# RELAY4.net
KiCad netlist of a schematic drawn in Altium Designer
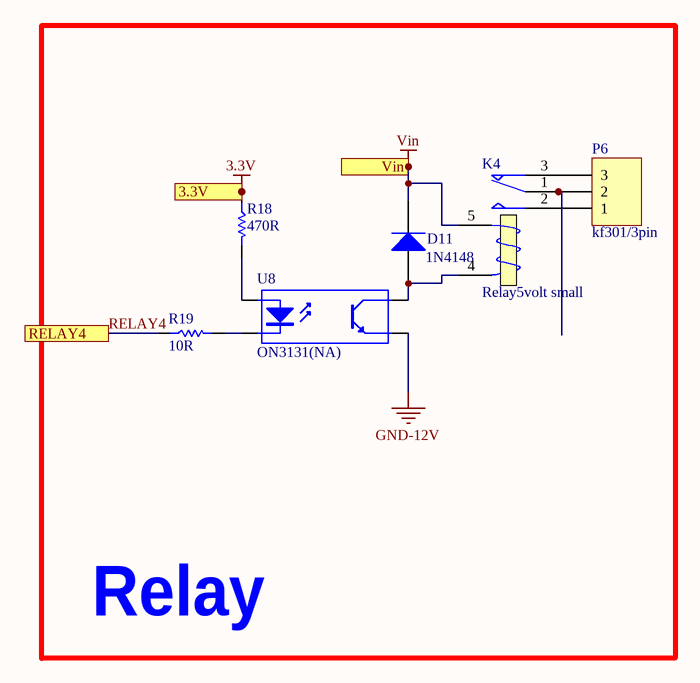
[diagram p0: RELAY4.SchDoc]

(export (version "E")
  (design (tool "Eeschema 10.0.6"))
  (components
    (comp (ref "D11")
      (value "1N4148")
      (footprint "sod123")
      (description "1 Amp General Purpose Rectifier")
      (fields (field (name "PUBLISHER") "Altium Limited"))
      (libsource (lib "Miscellaneous Devices") (part "Diode 1N4007"))
    )
    (comp (ref "K4")
      (value "Relay5volt small")
      (footprint "relay5_childern")
      (description "SPDT Relay")
      (fields (field (name "PUBLISHER") "Altium Limited"))
      (libsource (lib "FLIB") (part "Relay"))
    )
    (comp (ref "P6")
      (value "kf301/3pin")
      (footprint "Blue Connector 1*3 -kf301")
      (fields (field (name "PUBLISHER") "Altium Limited"))
      (libsource (lib "Miscellaneous Connectors") (part "Header 3"))
    )
    (comp (ref "R18")
      (value "470R")
      (footprint "0805/resistor")
      (description "Resistor")
      (fields (field (name "TOLERANCE") "5%") (field (name "POWER") "1/8 W"))
      (libsource (lib "skille") (part "Resistor"))
    )
    (comp (ref "R19")
      (value "10R")
      (footprint "0805/resistor")
      (description "Resistor")
      (fields (field (name "TOLERANCE") "5%") (field (name "POWER") "1/8 W"))
      (libsource (lib "skille") (part "Resistor"))
    )
    (comp (ref "U8")
      (value "ON3131(NA)")
      (footprint "OPTO_COUPLER")
      (description "4-Pin Phototransistor Optocoupler")
      (fields (field (name "PUBLISHER") "Altium Limited"))
      (libsource (lib "skille") (part "Optoisolator1"))
    )
  )
  (nets
    (net (code "1") (name "/RELAY4") (class "Default")
      (node (ref "R19") (pin "1") (pinfunction "1_1") (pintype "passive"))
    )
    (net (code "2") (name "3.3V") (class "Default")
      (node (ref "R18") (pin "1") (pinfunction "1_1") (pintype "passive"))
    )
    (net (code "3") (name "GND-12V") (class "Default")
      (node (ref "U8") (pin "3") (pinfunction "E_3") (pintype "passive"))
    )
    (net (code "4") (name "Net-(K4-COM)") (class "Default")
      (node (ref "K4") (pin "1") (pinfunction "COM_1") (pintype "passive"))
      (node (ref "P6") (pin "2") (pinfunction "2_2") (pintype "passive"))
    )
    (net (code "5") (name "Net-(K4-NO)") (class "Default")
      (node (ref "K4") (pin "2") (pinfunction "NO_2") (pintype "passive"))
      (node (ref "P6") (pin "1") (pinfunction "1_1") (pintype "passive"))
    )
    (net (code "6") (name "Net-(K4-T1)") (class "Default")
      (node (ref "K4") (pin "3") (pinfunction "T1_3") (pintype "passive"))
      (node (ref "P6") (pin "3") (pinfunction "3_3") (pintype "passive"))
    )
    (net (code "7") (name "Net-(K4-T2)") (class "Default")
      (node (ref "D11") (pin "A") (pinfunction "A_A") (pintype "passive"))
      (node (ref "K4") (pin "4") (pinfunction "T2_4") (pintype "passive"))
      (node (ref "U8") (pin "4") (pinfunction "C_4") (pintype "passive"))
    )
    (net (code "8") (name "Net-(U8-A)") (class "Default")
      (node (ref "R18") (pin "2") (pinfunction "2_2") (pintype "passive"))
      (node (ref "U8") (pin "1") (pinfunction "A_1") (pintype "passive"))
    )
    (net (code "9") (name "Net-(U8-K)") (class "Default")
      (node (ref "R19") (pin "2") (pinfunction "2_2") (pintype "passive"))
      (node (ref "U8") (pin "2") (pinfunction "K_2") (pintype "passive"))
    )
    (net (code "10") (name "Vin") (class "Default")
      (node (ref "D11") (pin "K") (pinfunction "K_K") (pintype "passive"))
      (node (ref "K4") (pin "5") (pinfunction "5_5") (pintype "passive"))
    )
  )
)
